# Robot_Arm_Board.net
KiCad netlist of a schematic drawn in EAGLE
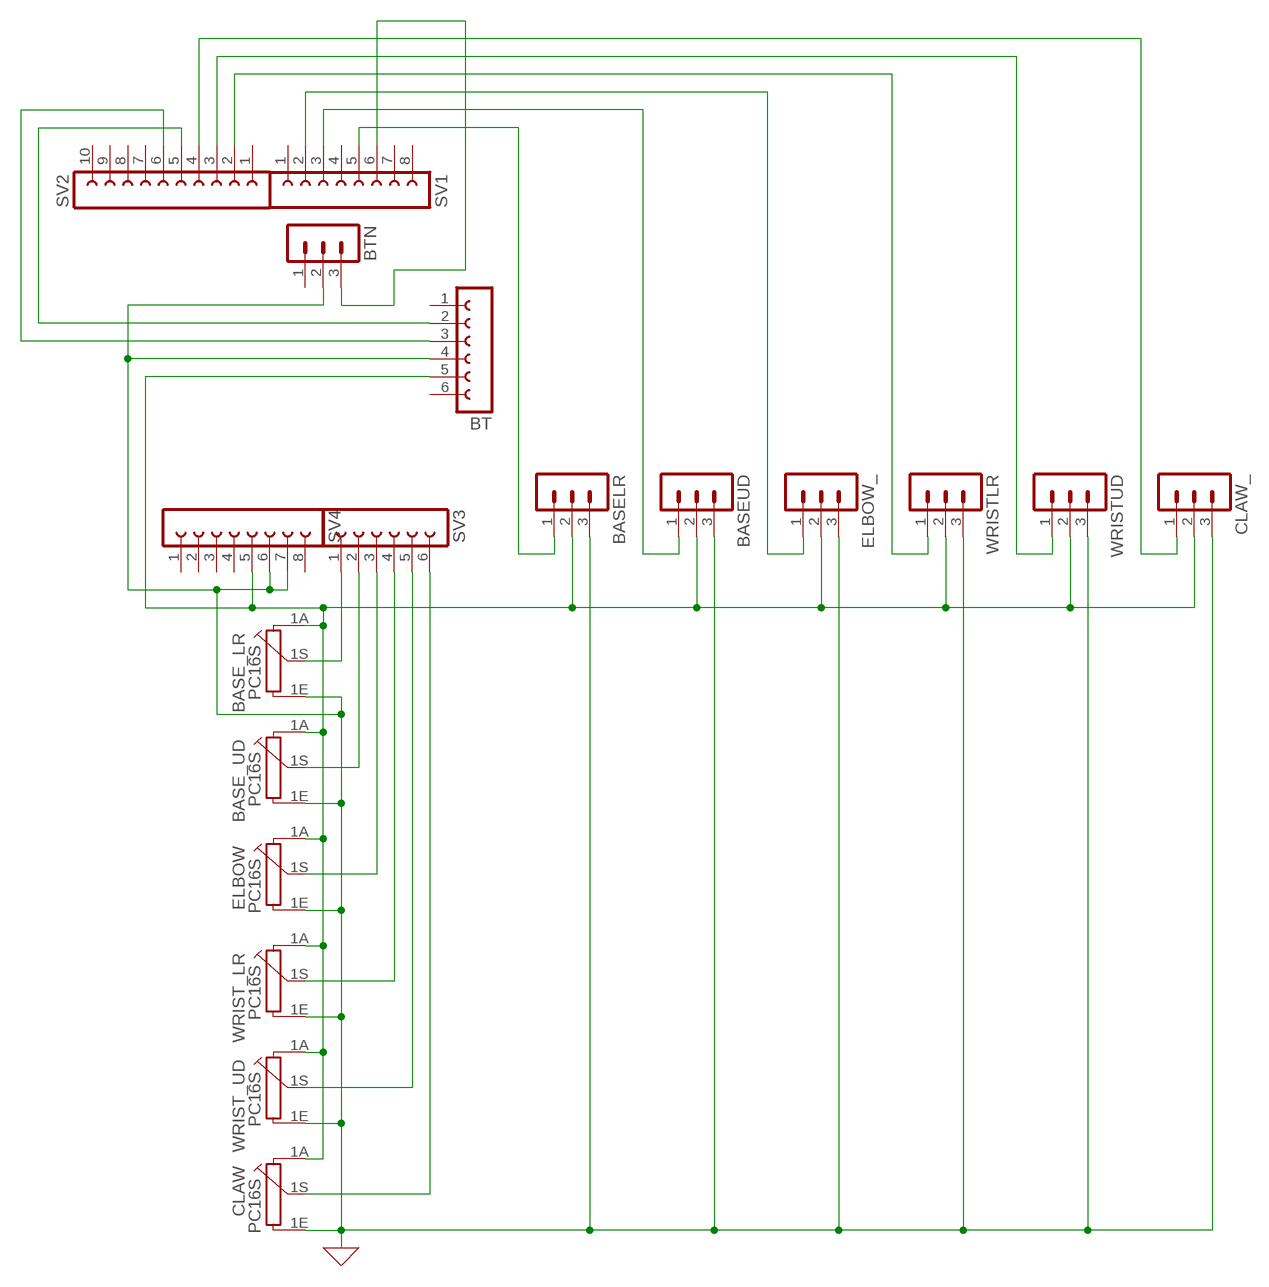
[diagram p0: schematic, sheet 1]

(export (version "E")
  (design (tool "Eeschema 10.0.6"))
  (components
    (comp (ref "BASELR")
      (value "MA03-1")
      (footprint "eagle-import:MA03-1")
      (libsource (lib "eagle-import") (part "MA03-1"))
    )
    (comp (ref "BASEUD")
      (value "MA03-1")
      (footprint "eagle-import:MA03-1")
      (libsource (lib "eagle-import") (part "MA03-1"))
    )
    (comp (ref "BASE_LR")
      (value "PC16S")
      (footprint "eagle-import:PC16S")
      (libsource (lib "eagle-import") (part "PC16S"))
    )
    (comp (ref "BASE_UD")
      (value "PC16S")
      (footprint "eagle-import:PC16S")
      (libsource (lib "eagle-import") (part "PC16S"))
    )
    (comp (ref "BT")
      (value "FE06-1")
      (footprint "eagle-import:FE06")
      (libsource (lib "eagle-import") (part "FE06-1"))
    )
    (comp (ref "BTN")
      (value "MA03-1")
      (footprint "eagle-import:MA03-1")
      (libsource (lib "eagle-import") (part "MA03-1"))
    )
    (comp (ref "CLAW")
      (value "PC16S")
      (footprint "eagle-import:PC16S")
      (libsource (lib "eagle-import") (part "PC16S"))
    )
    (comp (ref "CLAW_")
      (value "MA03-1")
      (footprint "eagle-import:MA03-1")
      (libsource (lib "eagle-import") (part "MA03-1"))
    )
    (comp (ref "ELBOW")
      (value "PC16S")
      (footprint "eagle-import:PC16S")
      (libsource (lib "eagle-import") (part "PC16S"))
    )
    (comp (ref "ELBOW_")
      (value "MA03-1")
      (footprint "eagle-import:MA03-1")
      (libsource (lib "eagle-import") (part "MA03-1"))
    )
    (comp (ref "SV1")
      (value "FE08-1")
      (footprint "eagle-import:FE08")
      (libsource (lib "eagle-import") (part "FE08-1"))
    )
    (comp (ref "SV2")
      (value "FE10-1")
      (footprint "eagle-import:FE10")
      (libsource (lib "eagle-import") (part "FE10-1"))
    )
    (comp (ref "SV3")
      (value "FE06-1")
      (footprint "eagle-import:FE06")
      (libsource (lib "eagle-import") (part "FE06-1"))
    )
    (comp (ref "SV4")
      (value "FE08-1")
      (footprint "eagle-import:FE08")
      (libsource (lib "eagle-import") (part "FE08-1"))
    )
    (comp (ref "WRISTLR")
      (value "MA03-1")
      (footprint "eagle-import:MA03-1")
      (libsource (lib "eagle-import") (part "MA03-1"))
    )
    (comp (ref "WRISTUD")
      (value "MA03-1")
      (footprint "eagle-import:MA03-1")
      (libsource (lib "eagle-import") (part "MA03-1"))
    )
    (comp (ref "WRIST_LR")
      (value "PC16S")
      (footprint "eagle-import:PC16S")
      (libsource (lib "eagle-import") (part "PC16S"))
    )
    (comp (ref "WRIST_UD")
      (value "PC16S")
      (footprint "eagle-import:PC16S")
      (libsource (lib "eagle-import") (part "PC16S"))
    )
  )
  (nets
    (net (code "1") (name "GND") (class "Default")
      (node (ref "BASELR") (pin "3") (pinfunction "3_3") (pintype "passive"))
      (node (ref "BASEUD") (pin "3") (pinfunction "3_3") (pintype "passive"))
      (node (ref "BASE_LR") (pin "1E") (pinfunction "1E_1E") (pintype "passive"))
      (node (ref "BASE_UD") (pin "1E") (pinfunction "1E_1E") (pintype "passive"))
      (node (ref "BT") (pin "4") (pinfunction "4_4") (pintype "passive"))
      (node (ref "BTN") (pin "2") (pinfunction "2_2") (pintype "passive"))
      (node (ref "CLAW") (pin "1E") (pinfunction "1E_1E") (pintype "passive"))
      (node (ref "CLAW_") (pin "3") (pinfunction "3_3") (pintype "passive"))
      (node (ref "ELBOW") (pin "1E") (pinfunction "1E_1E") (pintype "passive"))
      (node (ref "ELBOW_") (pin "3") (pinfunction "3_3") (pintype "passive"))
      (node (ref "SV4") (pin "6") (pinfunction "6_6") (pintype "passive"))
      (node (ref "SV4") (pin "7") (pinfunction "7_7") (pintype "passive"))
      (node (ref "WRISTLR") (pin "3") (pinfunction "3_3") (pintype "passive"))
      (node (ref "WRISTUD") (pin "3") (pinfunction "3_3") (pintype "passive"))
      (node (ref "WRIST_LR") (pin "1E") (pinfunction "1E_1E") (pintype "passive"))
      (node (ref "WRIST_UD") (pin "1E") (pinfunction "1E_1E") (pintype "passive"))
    )
    (net (code "2") (name "Net-(BASELR-Pad1)") (class "Default")
      (node (ref "BASELR") (pin "1") (pinfunction "1_1") (pintype "passive"))
      (node (ref "SV1") (pin "5") (pinfunction "5_5") (pintype "passive"))
    )
    (net (code "3") (name "Net-(BASELR-Pad2)") (class "Default")
      (node (ref "BASELR") (pin "2") (pinfunction "2_2") (pintype "passive"))
      (node (ref "BASEUD") (pin "2") (pinfunction "2_2") (pintype "passive"))
      (node (ref "BASE_LR") (pin "1A") (pinfunction "1A_1A") (pintype "passive"))
      (node (ref "BASE_UD") (pin "1A") (pinfunction "1A_1A") (pintype "passive"))
      (node (ref "BT") (pin "5") (pinfunction "5_5") (pintype "passive"))
      (node (ref "CLAW") (pin "1A") (pinfunction "1A_1A") (pintype "passive"))
      (node (ref "CLAW_") (pin "2") (pinfunction "2_2") (pintype "passive"))
      (node (ref "ELBOW") (pin "1A") (pinfunction "1A_1A") (pintype "passive"))
      (node (ref "ELBOW_") (pin "2") (pinfunction "2_2") (pintype "passive"))
      (node (ref "SV4") (pin "5") (pinfunction "5_5") (pintype "passive"))
      (node (ref "WRISTLR") (pin "2") (pinfunction "2_2") (pintype "passive"))
      (node (ref "WRISTUD") (pin "2") (pinfunction "2_2") (pintype "passive"))
      (node (ref "WRIST_LR") (pin "1A") (pinfunction "1A_1A") (pintype "passive"))
      (node (ref "WRIST_UD") (pin "1A") (pinfunction "1A_1A") (pintype "passive"))
    )
    (net (code "4") (name "Net-(BASEUD-Pad1)") (class "Default")
      (node (ref "BASEUD") (pin "1") (pinfunction "1_1") (pintype "passive"))
      (node (ref "SV1") (pin "3") (pinfunction "3_3") (pintype "passive"))
    )
    (net (code "5") (name "Net-(BASE_LR-Pad1S)") (class "Default")
      (node (ref "BASE_LR") (pin "1S") (pinfunction "1S_1S") (pintype "passive"))
      (node (ref "SV3") (pin "1") (pinfunction "1_1") (pintype "passive"))
    )
    (net (code "6") (name "Net-(BASE_UD-Pad1S)") (class "Default")
      (node (ref "BASE_UD") (pin "1S") (pinfunction "1S_1S") (pintype "passive"))
      (node (ref "SV3") (pin "2") (pinfunction "2_2") (pintype "passive"))
    )
    (net (code "7") (name "Net-(BT-Pad2)") (class "Default")
      (node (ref "BT") (pin "2") (pinfunction "2_2") (pintype "passive"))
      (node (ref "SV2") (pin "5") (pinfunction "5_5") (pintype "passive"))
    )
    (net (code "8") (name "Net-(BT-Pad3)") (class "Default")
      (node (ref "BT") (pin "3") (pinfunction "3_3") (pintype "passive"))
      (node (ref "SV2") (pin "6") (pinfunction "6_6") (pintype "passive"))
    )
    (net (code "9") (name "Net-(BTN-Pad3)") (class "Default")
      (node (ref "BTN") (pin "3") (pinfunction "3_3") (pintype "passive"))
      (node (ref "SV1") (pin "6") (pinfunction "6_6") (pintype "passive"))
    )
    (net (code "10") (name "Net-(CLAW-Pad1S)") (class "Default")
      (node (ref "CLAW") (pin "1S") (pinfunction "1S_1S") (pintype "passive"))
      (node (ref "SV3") (pin "6") (pinfunction "6_6") (pintype "passive"))
    )
    (net (code "11") (name "Net-(CLAW_-Pad1)") (class "Default")
      (node (ref "CLAW_") (pin "1") (pinfunction "1_1") (pintype "passive"))
      (node (ref "SV2") (pin "4") (pinfunction "4_4") (pintype "passive"))
    )
    (net (code "12") (name "Net-(ELBOW-Pad1S)") (class "Default")
      (node (ref "ELBOW") (pin "1S") (pinfunction "1S_1S") (pintype "passive"))
      (node (ref "SV3") (pin "3") (pinfunction "3_3") (pintype "passive"))
    )
    (net (code "13") (name "Net-(ELBOW_-Pad1)") (class "Default")
      (node (ref "ELBOW_") (pin "1") (pinfunction "1_1") (pintype "passive"))
      (node (ref "SV1") (pin "2") (pinfunction "2_2") (pintype "passive"))
    )
    (net (code "14") (name "Net-(SV2-Pad2)") (class "Default")
      (node (ref "SV2") (pin "2") (pinfunction "2_2") (pintype "passive"))
      (node (ref "WRISTLR") (pin "1") (pinfunction "1_1") (pintype "passive"))
    )
    (net (code "15") (name "Net-(SV2-Pad3)") (class "Default")
      (node (ref "SV2") (pin "3") (pinfunction "3_3") (pintype "passive"))
      (node (ref "WRISTUD") (pin "1") (pinfunction "1_1") (pintype "passive"))
    )
    (net (code "16") (name "Net-(SV3-Pad4)") (class "Default")
      (node (ref "SV3") (pin "4") (pinfunction "4_4") (pintype "passive"))
      (node (ref "WRIST_LR") (pin "1S") (pinfunction "1S_1S") (pintype "passive"))
    )
    (net (code "17") (name "Net-(SV3-Pad5)") (class "Default")
      (node (ref "SV3") (pin "5") (pinfunction "5_5") (pintype "passive"))
      (node (ref "WRIST_UD") (pin "1S") (pinfunction "1S_1S") (pintype "passive"))
    )
    (net (code "18") (name "unconnected-(BT-Pad1)") (class "Default")
      (node (ref "BT") (pin "1") (pinfunction "1_1") (pintype "passive"))
    )
    (net (code "19") (name "unconnected-(BT-Pad6)") (class "Default")
      (node (ref "BT") (pin "6") (pinfunction "6_6") (pintype "passive"))
    )
    (net (code "20") (name "unconnected-(BTN-Pad1)") (class "Default")
      (node (ref "BTN") (pin "1") (pinfunction "1_1") (pintype "passive"))
    )
    (net (code "21") (name "unconnected-(SV1-Pad1)") (class "Default")
      (node (ref "SV1") (pin "1") (pinfunction "1_1") (pintype "passive"))
    )
    (net (code "22") (name "unconnected-(SV1-Pad4)") (class "Default")
      (node (ref "SV1") (pin "4") (pinfunction "4_4") (pintype "passive"))
    )
    (net (code "23") (name "unconnected-(SV1-Pad7)") (class "Default")
      (node (ref "SV1") (pin "7") (pinfunction "7_7") (pintype "passive"))
    )
    (net (code "24") (name "unconnected-(SV1-Pad8)") (class "Default")
      (node (ref "SV1") (pin "8") (pinfunction "8_8") (pintype "passive"))
    )
    (net (code "25") (name "unconnected-(SV2-Pad1)") (class "Default")
      (node (ref "SV2") (pin "1") (pinfunction "1_1") (pintype "passive"))
    )
    (net (code "26") (name "unconnected-(SV2-Pad7)") (class "Default")
      (node (ref "SV2") (pin "7") (pinfunction "7_7") (pintype "passive"))
    )
    (net (code "27") (name "unconnected-(SV2-Pad8)") (class "Default")
      (node (ref "SV2") (pin "8") (pinfunction "8_8") (pintype "passive"))
    )
    (net (code "28") (name "unconnected-(SV2-Pad9)") (class "Default")
      (node (ref "SV2") (pin "9") (pinfunction "9_9") (pintype "passive"))
    )
    (net (code "29") (name "unconnected-(SV2-Pad10)") (class "Default")
      (node (ref "SV2") (pin "10") (pinfunction "10_10") (pintype "passive"))
    )
    (net (code "30") (name "unconnected-(SV4-Pad1)") (class "Default")
      (node (ref "SV4") (pin "1") (pinfunction "1_1") (pintype "passive"))
    )
    (net (code "31") (name "unconnected-(SV4-Pad2)") (class "Default")
      (node (ref "SV4") (pin "2") (pinfunction "2_2") (pintype "passive"))
    )
    (net (code "32") (name "unconnected-(SV4-Pad3)") (class "Default")
      (node (ref "SV4") (pin "3") (pinfunction "3_3") (pintype "passive"))
    )
    (net (code "33") (name "unconnected-(SV4-Pad4)") (class "Default")
      (node (ref "SV4") (pin "4") (pinfunction "4_4") (pintype "passive"))
    )
    (net (code "34") (name "unconnected-(SV4-Pad8)") (class "Default")
      (node (ref "SV4") (pin "8") (pinfunction "8_8") (pintype "passive"))
    )
  )
)
